# design.net
KiCad netlist of a schematic drawn in Altium Designer
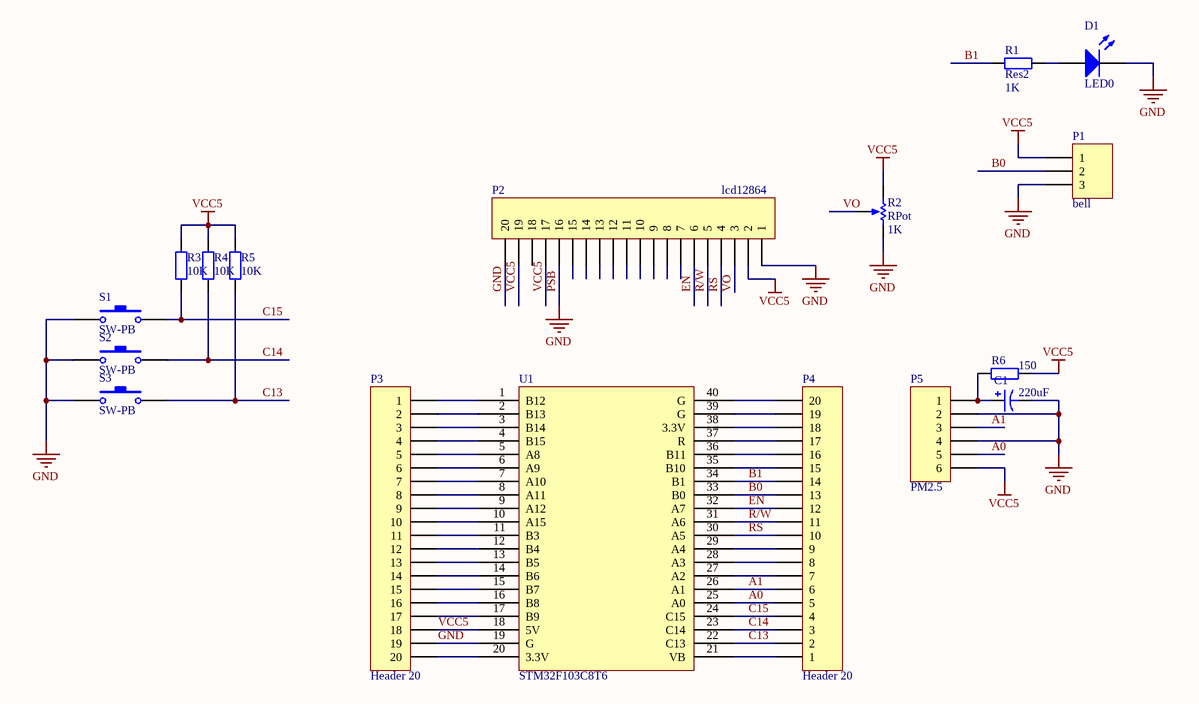
[diagram p0: 基于单片机的无线红外防盗报警系统原理图.SchDoc]

(export (version "E")
  (design (tool "Eeschema 10.0.6"))
  (components
    (comp (ref "C1")
      (value "220uF")
      (footprint "RB.1/.3A")
      (description "Polarized Capacitor (Radial)")
      (fields (field (name "Comment") "Cap Pol1") (field (name "PUBLISHER") "Altium Limited"))
      (libsource (lib "Miscellaneous Devices") (part "Cap Pol1"))
    )
    (comp (ref "D1")
      (value "LED0")
      (footprint "LED0.1")
      (description "Typical INFRARED GaAs LED")
      (fields (field (name "PUBLISHER") "Altium Limited"))
      (libsource (lib "Miscellaneous Devices") (part "LED0"))
    )
    (comp (ref "P1")
      (value "bell")
      (footprint "HDR1X3")
      (description "Header, 3-Pin")
      (fields (field (name "PUBLISHER") "Altium Limited"))
      (libsource (lib "Miscellaneous Connectors") (part "Header 3"))
    )
    (comp (ref "P2")
      (value "lcd12864")
      (footprint "HDR1X20")
      (description "Header, 20-Pin")
      (fields (field (name "PUBLISHER") "Altium Limited"))
      (libsource (lib "Miscellaneous Connectors") (part "Header 20"))
    )
    (comp (ref "P3")
      (value "Header 20")
      (footprint "HDR1X20")
      (description "Header, 20-Pin")
      (fields (field (name "PUBLISHER") "Altium Limited"))
      (libsource (lib "") (part "Header 20_2"))
    )
    (comp (ref "P4")
      (value "Header 20")
      (footprint "HDR1X20")
      (description "Header, 20-Pin")
      (fields (field (name "PUBLISHER") "Altium Limited"))
      (libsource (lib "") (part "Header 20_1"))
    )
    (comp (ref "P5")
      (value "PM2.5")
      (footprint "HDR1X6")
      (description "Header, 6-Pin")
      (fields (field (name "PUBLISHER") "Altium Limited"))
      (libsource (lib "Miscellaneous Connectors") (part "Header 6"))
    )
    (comp (ref "R1")
      (value "Res2")
      (footprint "0805")
      (description "Resistor")
      (fields (field (name "ALTIUM_VALUE") "1K") (field (name "PUBLISHER") "Altium Limited"))
      (libsource (lib "") (part "Res2_1"))
    )
    (comp (ref "R2")
      (value "RPot")
      (footprint "VR5")
      (description "Potentiometer")
      (fields (field (name "ALTIUM_VALUE") "1K") (field (name "PUBLISHER") "Altium Limited"))
      (libsource (lib "Miscellaneous Devices") (part "RPot"))
    )
    (comp (ref "R3")
      (value "10K")
      (footprint "LC-0805_R")
      (description "Resistor")
      (fields (field (name "Comment") "Res2") (field (name "PUBLISHER") "Altium Limited"))
      (libsource (lib "Miscellaneous Devices") (part "Res2"))
    )
    (comp (ref "R4")
      (value "10K")
      (footprint "LC-0805_R")
      (description "Resistor")
      (fields (field (name "Comment") "Res2") (field (name "PUBLISHER") "Altium Limited"))
      (libsource (lib "Miscellaneous Devices") (part "Res2"))
    )
    (comp (ref "R5")
      (value "10K")
      (footprint "LC-0805_R")
      (description "Resistor")
      (fields (field (name "Comment") "Res2") (field (name "PUBLISHER") "Altium Limited"))
      (libsource (lib "Miscellaneous Devices") (part "Res2"))
    )
    (comp (ref "R6")
      (value "150")
      (footprint "LC-0805_R")
      (description "Resistor")
      (fields (field (name "Comment") "Res2") (field (name "PUBLISHER") "Altium Limited"))
      (libsource (lib "") (part "Res2_1"))
    )
    (comp (ref "S1")
      (value "SW-PB")
      (footprint "SW-PB2")
      (description "Switch")
      (fields (field (name "PUBLISHER") "Altium Limited"))
      (libsource (lib "Miscellaneous Devices") (part "SW-PB"))
    )
    (comp (ref "S2")
      (value "SW-PB")
      (footprint "SW-PB2")
      (description "Switch")
      (fields (field (name "PUBLISHER") "Altium Limited"))
      (libsource (lib "Miscellaneous Devices") (part "SW-PB"))
    )
    (comp (ref "S3")
      (value "SW-PB")
      (footprint "SW-PB2")
      (description "Switch")
      (fields (field (name "PUBLISHER") "Altium Limited"))
      (libsource (lib "Miscellaneous Devices") (part "SW-PB"))
    )
    (comp (ref "U1")
      (value "STM32F103C8T6")
      (footprint "132")
      (libsource (lib "stm32f103c8t6最小系统板") (part "Component_1"))
    )
  )
  (nets
    (net (code "1") (name "/A0") (class "Default")
      (node (ref "P4") (pin "5") (pinfunction "5_5") (pintype "passive"))
      (node (ref "P5") (pin "5") (pinfunction "5_5") (pintype "passive"))
      (node (ref "U1") (pin "25") (pinfunction "A0_25") (pintype "passive"))
    )
    (net (code "2") (name "/A1") (class "Default")
      (node (ref "P4") (pin "6") (pinfunction "6_6") (pintype "passive"))
      (node (ref "P5") (pin "3") (pinfunction "3_3") (pintype "passive"))
      (node (ref "U1") (pin "26") (pinfunction "A1_26") (pintype "passive"))
    )
    (net (code "3") (name "/B0") (class "Default")
      (node (ref "P1") (pin "2") (pinfunction "2_2") (pintype "passive"))
      (node (ref "P4") (pin "13") (pinfunction "13_13") (pintype "passive"))
      (node (ref "U1") (pin "33") (pinfunction "B0_33") (pintype "passive"))
    )
    (net (code "4") (name "/B1") (class "Default")
      (node (ref "P4") (pin "14") (pinfunction "14_14") (pintype "passive"))
      (node (ref "R1") (pin "1") (pinfunction "1_1") (pintype "passive"))
      (node (ref "U1") (pin "34") (pinfunction "B1_34") (pintype "passive"))
    )
    (net (code "5") (name "/C13") (class "Default")
      (node (ref "P4") (pin "2") (pinfunction "2_2") (pintype "passive"))
      (node (ref "R5") (pin "1") (pinfunction "1_1") (pintype "passive"))
      (node (ref "S3") (pin "2") (pinfunction "2_2") (pintype "passive"))
      (node (ref "U1") (pin "22") (pinfunction "C13_22") (pintype "passive"))
    )
    (net (code "6") (name "/C14") (class "Default")
      (node (ref "P4") (pin "3") (pinfunction "3_3") (pintype "passive"))
      (node (ref "R4") (pin "1") (pinfunction "1_1") (pintype "passive"))
      (node (ref "S2") (pin "2") (pinfunction "2_2") (pintype "passive"))
      (node (ref "U1") (pin "23") (pinfunction "C14_23") (pintype "passive"))
    )
    (net (code "7") (name "/C15") (class "Default")
      (node (ref "P4") (pin "4") (pinfunction "4_4") (pintype "passive"))
      (node (ref "R3") (pin "1") (pinfunction "1_1") (pintype "passive"))
      (node (ref "S1") (pin "2") (pinfunction "2_2") (pintype "passive"))
      (node (ref "U1") (pin "24") (pinfunction "C15_24") (pintype "passive"))
    )
    (net (code "8") (name "/EN") (class "Default")
      (node (ref "P2") (pin "6") (pinfunction "6_6") (pintype "passive"))
      (node (ref "P4") (pin "12") (pinfunction "12_12") (pintype "passive"))
      (node (ref "U1") (pin "32") (pinfunction "A7_32") (pintype "passive"))
    )
    (net (code "9") (name "/RS") (class "Default")
      (node (ref "P2") (pin "4") (pinfunction "4_4") (pintype "passive"))
      (node (ref "P4") (pin "10") (pinfunction "10_10") (pintype "passive"))
      (node (ref "U1") (pin "30") (pinfunction "A5_30") (pintype "passive"))
    )
    (net (code "10") (name "/R{slash}W") (class "Default")
      (node (ref "P2") (pin "5") (pinfunction "5_5") (pintype "passive"))
      (node (ref "P4") (pin "11") (pinfunction "11_11") (pintype "passive"))
      (node (ref "U1") (pin "31") (pinfunction "A6_31") (pintype "passive"))
    )
    (net (code "11") (name "/VO") (class "Default")
      (node (ref "P2") (pin "3") (pinfunction "3_3") (pintype "passive"))
      (node (ref "R2") (pin "3") (pinfunction "TAP_3") (pintype "passive"))
    )
    (net (code "12") (name "GND") (class "Default")
      (node (ref "C1") (pin "2") (pinfunction "2_2") (pintype "passive"))
      (node (ref "D1") (pin "2") (pinfunction "K_2") (pintype "passive"))
      (node (ref "P1") (pin "3") (pinfunction "3_3") (pintype "passive"))
      (node (ref "P2") (pin "1") (pinfunction "1_1") (pintype "passive"))
      (node (ref "P2") (pin "16") (pinfunction "16_16") (pintype "passive"))
      (node (ref "P2") (pin "20") (pinfunction "20_20") (pintype "passive"))
      (node (ref "P3") (pin "19") (pinfunction "19_19") (pintype "passive"))
      (node (ref "P5") (pin "2") (pinfunction "2_2") (pintype "passive"))
      (node (ref "P5") (pin "4") (pinfunction "4_4") (pintype "passive"))
      (node (ref "R2") (pin "2") (pinfunction "BOT_2") (pintype "passive"))
      (node (ref "S1") (pin "1") (pinfunction "1_1") (pintype "passive"))
      (node (ref "S2") (pin "1") (pinfunction "1_1") (pintype "passive"))
      (node (ref "S3") (pin "1") (pinfunction "1_1") (pintype "passive"))
      (node (ref "U1") (pin "19") (pinfunction "G_19") (pintype "passive"))
    )
    (net (code "13") (name "Net-(C1-Pad1)") (class "Default")
      (node (ref "C1") (pin "1") (pinfunction "1_1") (pintype "passive"))
      (node (ref "P5") (pin "1") (pinfunction "1_1") (pintype "passive"))
      (node (ref "R6") (pin "1") (pinfunction "1_1") (pintype "passive"))
    )
    (net (code "14") (name "Net-(D1-A)") (class "Default")
      (node (ref "D1") (pin "1") (pinfunction "A_1") (pintype "passive"))
      (node (ref "R1") (pin "2") (pinfunction "2_2") (pintype "passive"))
    )
    (net (code "15") (name "Net-(P3-Pad20)") (class "Default")
      (node (ref "P3") (pin "20") (pinfunction "20_20") (pintype "passive"))
      (node (ref "U1") (pin "20") (pinfunction "3.3V_20") (pintype "passive"))
    )
    (net (code "16") (name "Net-(P4-Pad18)") (class "Default")
      (node (ref "P4") (pin "18") (pinfunction "18_18") (pintype "passive"))
      (node (ref "U1") (pin "38") (pinfunction "3.3V_38") (pintype "passive"))
    )
    (net (code "17") (name "Net-(P4-Pad19)") (class "Default")
      (node (ref "P4") (pin "19") (pinfunction "19_19") (pintype "passive"))
      (node (ref "U1") (pin "39") (pinfunction "G_39") (pintype "passive"))
    )
    (net (code "18") (name "Net-(P4-Pad20)") (class "Default")
      (node (ref "P4") (pin "20") (pinfunction "20_20") (pintype "passive"))
      (node (ref "U1") (pin "40") (pinfunction "G_40") (pintype "passive"))
    )
    (net (code "19") (name "Net-(U1-A2)") (class "Default")
      (node (ref "P4") (pin "7") (pinfunction "7_7") (pintype "passive"))
      (node (ref "U1") (pin "27") (pinfunction "A2_27") (pintype "passive"))
    )
    (net (code "20") (name "Net-(U1-A3)") (class "Default")
      (node (ref "P4") (pin "8") (pinfunction "8_8") (pintype "passive"))
      (node (ref "U1") (pin "28") (pinfunction "A3_28") (pintype "passive"))
    )
    (net (code "21") (name "Net-(U1-A4)") (class "Default")
      (node (ref "P4") (pin "9") (pinfunction "9_9") (pintype "passive"))
      (node (ref "U1") (pin "29") (pinfunction "A4_29") (pintype "passive"))
    )
    (net (code "22") (name "Net-(U1-A8)") (class "Default")
      (node (ref "P3") (pin "5") (pinfunction "5_5") (pintype "passive"))
      (node (ref "U1") (pin "5") (pinfunction "A8_5") (pintype "passive"))
    )
    (net (code "23") (name "Net-(U1-A9)") (class "Default")
      (node (ref "P3") (pin "6") (pinfunction "6_6") (pintype "passive"))
      (node (ref "U1") (pin "6") (pinfunction "A9_6") (pintype "passive"))
    )
    (net (code "24") (name "Net-(U1-A10)") (class "Default")
      (node (ref "P3") (pin "7") (pinfunction "7_7") (pintype "passive"))
      (node (ref "U1") (pin "7") (pinfunction "A10_7") (pintype "passive"))
    )
    (net (code "25") (name "Net-(U1-A11)") (class "Default")
      (node (ref "P3") (pin "8") (pinfunction "8_8") (pintype "passive"))
      (node (ref "U1") (pin "8") (pinfunction "A11_8") (pintype "passive"))
    )
    (net (code "26") (name "Net-(U1-A12)") (class "Default")
      (node (ref "P3") (pin "9") (pinfunction "9_9") (pintype "passive"))
      (node (ref "U1") (pin "9") (pinfunction "A12_9") (pintype "passive"))
    )
    (net (code "27") (name "Net-(U1-A15)") (class "Default")
      (node (ref "P3") (pin "10") (pinfunction "10_10") (pintype "passive"))
      (node (ref "U1") (pin "10") (pinfunction "A15_10") (pintype "passive"))
    )
    (net (code "28") (name "Net-(U1-B3)") (class "Default")
      (node (ref "P3") (pin "11") (pinfunction "11_11") (pintype "passive"))
      (node (ref "U1") (pin "11") (pinfunction "B3_11") (pintype "passive"))
    )
    (net (code "29") (name "Net-(U1-B4)") (class "Default")
      (node (ref "P3") (pin "12") (pinfunction "12_12") (pintype "passive"))
      (node (ref "U1") (pin "12") (pinfunction "B4_12") (pintype "passive"))
    )
    (net (code "30") (name "Net-(U1-B5)") (class "Default")
      (node (ref "P3") (pin "13") (pinfunction "13_13") (pintype "passive"))
      (node (ref "U1") (pin "13") (pinfunction "B5_13") (pintype "passive"))
    )
    (net (code "31") (name "Net-(U1-B6)") (class "Default")
      (node (ref "P3") (pin "14") (pinfunction "14_14") (pintype "passive"))
      (node (ref "U1") (pin "14") (pinfunction "B6_14") (pintype "passive"))
    )
    (net (code "32") (name "Net-(U1-B7)") (class "Default")
      (node (ref "P3") (pin "15") (pinfunction "15_15") (pintype "passive"))
      (node (ref "U1") (pin "15") (pinfunction "B7_15") (pintype "passive"))
    )
    (net (code "33") (name "Net-(U1-B8)") (class "Default")
      (node (ref "P3") (pin "16") (pinfunction "16_16") (pintype "passive"))
      (node (ref "U1") (pin "16") (pinfunction "B8_16") (pintype "passive"))
    )
    (net (code "34") (name "Net-(U1-B9)") (class "Default")
      (node (ref "P3") (pin "17") (pinfunction "17_17") (pintype "passive"))
      (node (ref "U1") (pin "17") (pinfunction "B9_17") (pintype "passive"))
    )
    (net (code "35") (name "Net-(U1-B10)") (class "Default")
      (node (ref "P4") (pin "15") (pinfunction "15_15") (pintype "passive"))
      (node (ref "U1") (pin "35") (pinfunction "B10_35") (pintype "passive"))
    )
    (net (code "36") (name "Net-(U1-B11)") (class "Default")
      (node (ref "P4") (pin "16") (pinfunction "16_16") (pintype "passive"))
      (node (ref "U1") (pin "36") (pinfunction "B11_36") (pintype "passive"))
    )
    (net (code "37") (name "Net-(U1-B12)") (class "Default")
      (node (ref "P3") (pin "1") (pinfunction "1_1") (pintype "passive"))
      (node (ref "U1") (pin "1") (pinfunction "B12_1") (pintype "passive"))
    )
    (net (code "38") (name "Net-(U1-B13)") (class "Default")
      (node (ref "P3") (pin "2") (pinfunction "2_2") (pintype "passive"))
      (node (ref "U1") (pin "2") (pinfunction "B13_2") (pintype "passive"))
    )
    (net (code "39") (name "Net-(U1-B14)") (class "Default")
      (node (ref "P3") (pin "3") (pinfunction "3_3") (pintype "passive"))
      (node (ref "U1") (pin "3") (pinfunction "B14_3") (pintype "passive"))
    )
    (net (code "40") (name "Net-(U1-B15)") (class "Default")
      (node (ref "P3") (pin "4") (pinfunction "4_4") (pintype "passive"))
      (node (ref "U1") (pin "4") (pinfunction "B15_4") (pintype "passive"))
    )
    (net (code "41") (name "Net-(U1-R)") (class "Default")
      (node (ref "P4") (pin "17") (pinfunction "17_17") (pintype "passive"))
      (node (ref "U1") (pin "37") (pinfunction "R_37") (pintype "passive"))
    )
    (net (code "42") (name "Net-(U1-VB)") (class "Default")
      (node (ref "P4") (pin "1") (pinfunction "1_1") (pintype "passive"))
      (node (ref "U1") (pin "21") (pinfunction "VB_21") (pintype "passive"))
    )
    (net (code "43") (name "VCC5") (class "Default")
      (node (ref "P1") (pin "1") (pinfunction "1_1") (pintype "passive"))
      (node (ref "P2") (pin "17") (pinfunction "17_17") (pintype "passive"))
      (node (ref "P2") (pin "19") (pinfunction "19_19") (pintype "passive"))
      (node (ref "P2") (pin "2") (pinfunction "2_2") (pintype "passive"))
      (node (ref "P3") (pin "18") (pinfunction "18_18") (pintype "passive"))
      (node (ref "P5") (pin "6") (pinfunction "6_6") (pintype "passive"))
      (node (ref "R2") (pin "1") (pinfunction "TOP_1") (pintype "passive"))
      (node (ref "R3") (pin "2") (pinfunction "2_2") (pintype "passive"))
      (node (ref "R4") (pin "2") (pinfunction "2_2") (pintype "passive"))
      (node (ref "R5") (pin "2") (pinfunction "2_2") (pintype "passive"))
      (node (ref "R6") (pin "2") (pinfunction "2_2") (pintype "passive"))
      (node (ref "U1") (pin "18") (pinfunction "5V_18") (pintype "passive"))
    )
    (net (code "44") (name "unconnected-(P2-Pad7)") (class "Default")
      (node (ref "P2") (pin "7") (pinfunction "7_7") (pintype "passive"))
    )
    (net (code "45") (name "unconnected-(P2-Pad8)") (class "Default")
      (node (ref "P2") (pin "8") (pinfunction "8_8") (pintype "passive"))
    )
    (net (code "46") (name "unconnected-(P2-Pad9)") (class "Default")
      (node (ref "P2") (pin "9") (pinfunction "9_9") (pintype "passive"))
    )
    (net (code "47") (name "unconnected-(P2-Pad10)") (class "Default")
      (node (ref "P2") (pin "10") (pinfunction "10_10") (pintype "passive"))
    )
    (net (code "48") (name "unconnected-(P2-Pad11)") (class "Default")
      (node (ref "P2") (pin "11") (pinfunction "11_11") (pintype "passive"))
    )
    (net (code "49") (name "unconnected-(P2-Pad12)") (class "Default")
      (node (ref "P2") (pin "12") (pinfunction "12_12") (pintype "passive"))
    )
    (net (code "50") (name "unconnected-(P2-Pad13)") (class "Default")
      (node (ref "P2") (pin "13") (pinfunction "13_13") (pintype "passive"))
    )
    (net (code "51") (name "unconnected-(P2-Pad14)") (class "Default")
      (node (ref "P2") (pin "14") (pinfunction "14_14") (pintype "passive"))
    )
    (net (code "52") (name "unconnected-(P2-Pad15)") (class "Default")
      (node (ref "P2") (pin "15") (pinfunction "15_15") (pintype "passive"))
    )
    (net (code "53") (name "unconnected-(P2-Pad18)") (class "Default")
      (node (ref "P2") (pin "18") (pinfunction "18_18") (pintype "passive"))
    )
  )
)
